# Sensor_Glove_Power-X02.net
KiCad netlist of a schematic drawn in Altium Designer
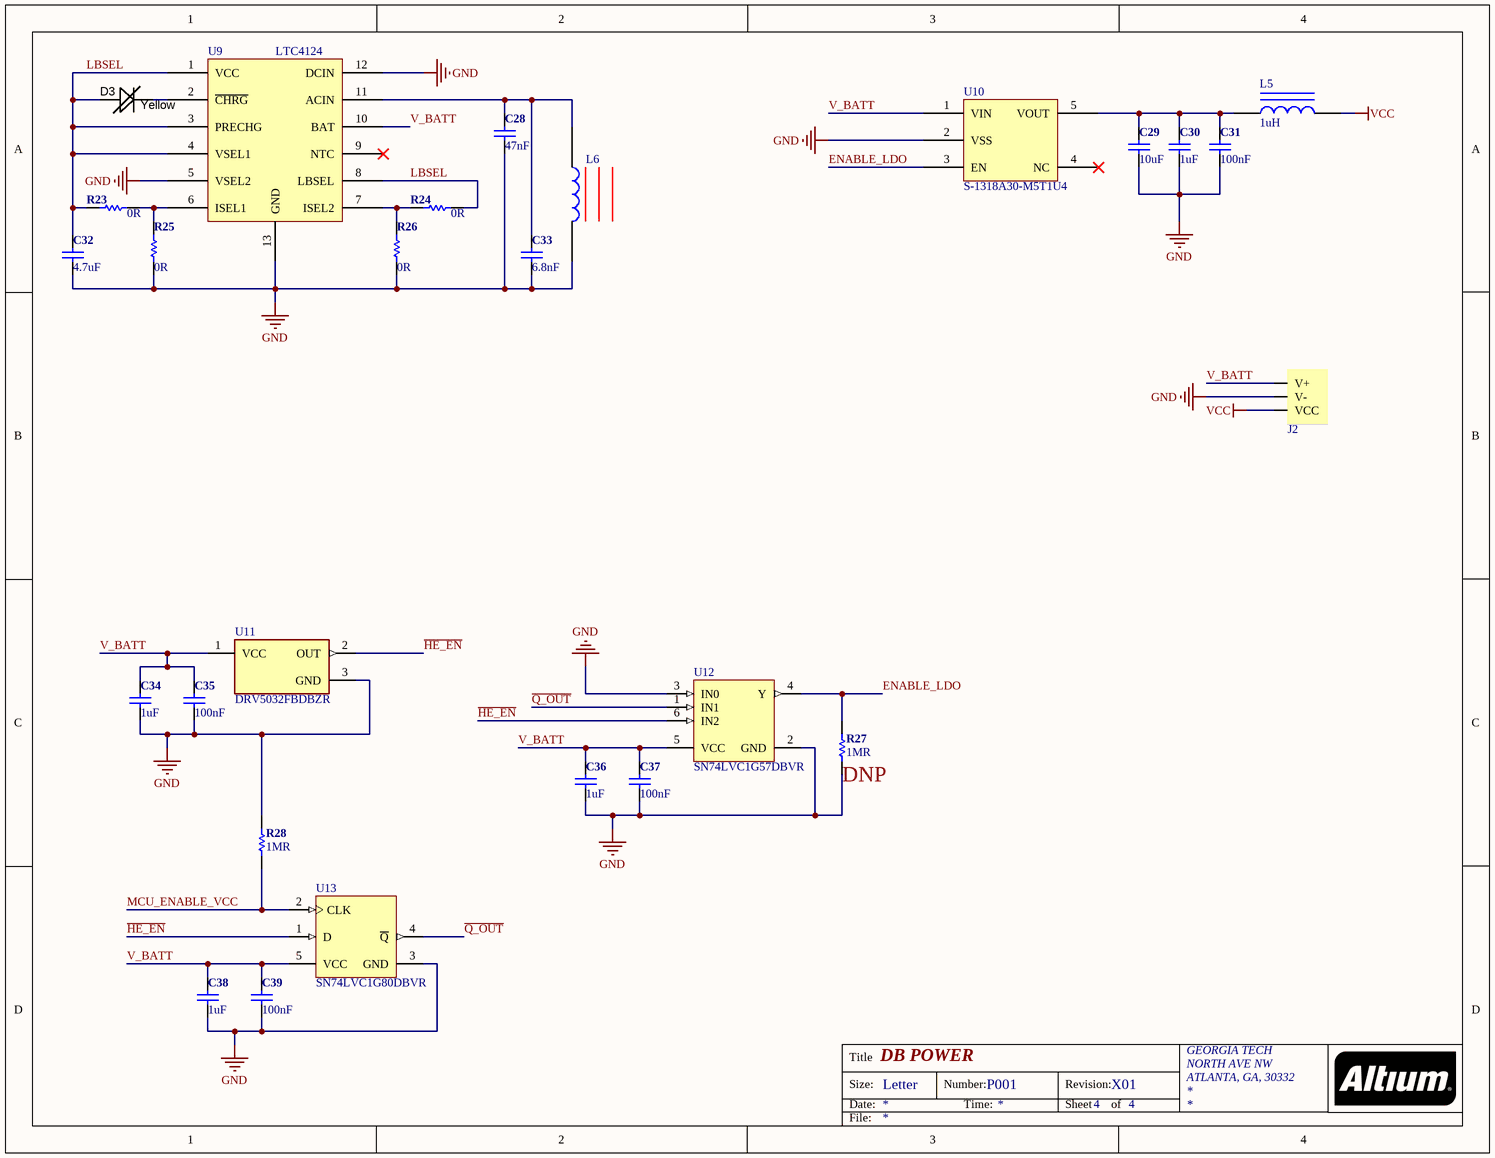
[diagram p0: Sensor_Glove_Power-X02.SchDoc]

(export (version "E")
  (design (tool "Eeschema 10.0.6"))
  (components
    (comp (ref "C28")
      (value "47nF")
      (footprint "C0402")
      (fields
        (field (name "MANUFACTURER") "Murata")
        (field (name "MANUFACTURER PART NUMBER") "GCM155R71H473KE02D")
      )
      (libsource (lib "LP_ECG-X02") (part "C-0402(1005)"))
    )
    (comp (ref "C29")
      (value "10uF")
      (footprint "C0402")
      (fields
        (field (name "MANUFACTURER") "Kyocera AVX")
        (field (name "MANUFACTURER PART NUMBER") "0402ZD106MAT2A")
      )
      (libsource (lib "LP_ECG-X01") (part "C-0402(1005)"))
    )
    (comp (ref "C30")
      (value "1uF")
      (footprint "C0402")
      (fields
        (field (name "MANUFACTURER") "Yageo")
        (field (name "MANUFACTURER PART NUMBER") "CC0402MRX5R5BB105")
        (field (name "TOLERANCE") "20%")
      )
      (libsource (lib "LP_ECG-X01") (part "C-0402(1005)"))
    )
    (comp (ref "C31")
      (value "100nF")
      (footprint "C0402")
      (fields
        (field (name "MANUFACTURER") "Taiyo Yuden")
        (field (name "MANUFACTURER PART NUMBER") "TMK105BJ104KV-F")
        (field (name "TOLERANCE") "10%")
      )
      (libsource (lib "LP_ECG-X01") (part "C-0402(1005)"))
    )
    (comp (ref "C32")
      (value "4.7uF")
      (footprint "C0402")
      (fields
        (field (name "MANUFACTURER") "Murata")
        (field (name "MANUFACTURER PART NUMBER") "GRM155R60J475ME87J")
      )
      (libsource (lib "LP_ECG-X02") (part "C-0402(1005)"))
    )
    (comp (ref "C33")
      (value "6.8nF")
      (footprint "C0402")
      (fields
        (field (name "MANUFACTURER") "Murata")
        (field (name "MANUFACTURER PART NUMBER") "GCM155R71H682KA55D")
      )
      (libsource (lib "LP_ECG-X02") (part "C-0402(1005)"))
    )
    (comp (ref "C34")
      (value "1uF")
      (footprint "C0402")
      (fields
        (field (name "MANUFACTURER") "Yageo")
        (field (name "MANUFACTURER PART NUMBER") "CC0402MRX5R5BB105")
        (field (name "TOLERANCE") "20%")
      )
      (libsource (lib "Sensor_Glove-X02") (part "C-0402(1005)"))
    )
    (comp (ref "C35")
      (value "100nF")
      (footprint "C0402")
      (fields
        (field (name "MANUFACTURER") "Taiyo Yuden")
        (field (name "MANUFACTURER PART NUMBER") "TMK105BJ104KV-F")
        (field (name "TOLERANCE") "10%")
      )
      (libsource (lib "LP_ECG-X01") (part "C-0402(1005)"))
    )
    (comp (ref "C36")
      (value "1uF")
      (footprint "C0402")
      (fields
        (field (name "MANUFACTURER") "Yageo")
        (field (name "MANUFACTURER PART NUMBER") "CC0402MRX5R5BB105")
        (field (name "TOLERANCE") "20%")
      )
      (libsource (lib "Sensor_Glove-X02") (part "C-0402(1005)"))
    )
    (comp (ref "C37")
      (value "100nF")
      (footprint "C0402")
      (fields
        (field (name "MANUFACTURER") "Taiyo Yuden")
        (field (name "MANUFACTURER PART NUMBER") "TMK105BJ104KV-F")
        (field (name "TOLERANCE") "10%")
      )
      (libsource (lib "LP_ECG-X01") (part "C-0402(1005)"))
    )
    (comp (ref "C38")
      (value "1uF")
      (footprint "C0402")
      (fields
        (field (name "MANUFACTURER") "Yageo")
        (field (name "MANUFACTURER PART NUMBER") "CC0402MRX5R5BB105")
        (field (name "TOLERANCE") "20%")
      )
      (libsource (lib "LP_ECG-X01") (part "C-0402(1005)"))
    )
    (comp (ref "C39")
      (value "100nF")
      (footprint "C0402")
      (fields
        (field (name "MANUFACTURER") "Taiyo Yuden")
        (field (name "MANUFACTURER PART NUMBER") "TMK105BJ104KV-F")
        (field (name "TOLERANCE") "10%")
      )
      (libsource (lib "LP_ECG-X01") (part "C-0402(1005)"))
    )
    (comp (ref "D3")
      (value "Yellow")
      (footprint "LED_0402")
      (description "Single Color LED, Super Bright Yellow, Water Clear, 0.8mm")
      (fields
        (field (name "MANUFACTURER") "Kingbright")
        (field (name "MANUFACTURER PART NUMBER") "APHHS1005SYCK")
      )
      (libsource (lib "Sensor_Glove-X02") (part "LED_0402(1005)"))
    )
    (comp (ref "J2")
      (value "SMD CONNECTOR FOR 40 mAh BATTERY")
      (footprint "battery_connector")
      (description "Lithium Battery 3.7V 40mAh Rechargeable")
      (libsource (lib "LP_ECG-X01") (part "SMD_BATTERY_CONNECTOR"))
    )
    (comp (ref "L5")
      (value "1uH")
      (footprint "L0402")
      (description "General Purpose Inductor, 1uH, 20%, 1 Element, Ferrite-Core, SMD, 0402")
      (fields
        (field (name "MANUFACTURER") "TDK")
        (field (name "MANUFACTURER PART NUMBER") "MLZ1005M1R0WT000")
      )
      (libsource (lib "LP_ECG-X01") (part "Inductor Iron"))
    )
    (comp (ref "L6")
      (value "WIRELESS CHARGING COIL, RECEIVER")
      (footprint "760308101219")
      (description "General Purpose Inductor, 11.8uH, 10%, 1 Element")
      (fields
        (field (name "MANUFACTURER") "Wurth Electronics")
        (field (name "MANUFACTURER PART NUMBER") "760308101219")
      )
      (libsource (lib "Sensor_Glove-X02") (part "WIRELESS_CHARGING_COIL"))
    )
    (comp (ref "R23")
      (value "0R")
      (footprint "R0402")
      (description "Fixed Resistor, Metal Glaze/thick Film, 0.0625W, 0ohm, Surface Mount, 0402")
      (fields
        (field (name "MANUFACTURER") "Yageo")
        (field (name "MANUFACTURER PART NUMBER") "AC0402JR-070RL")
      )
      (libsource (lib "LP_ECG-X02") (part "R-0402(1005)"))
    )
    (comp (ref "R24")
      (value "0R")
      (footprint "R0402")
      (description "Fixed Resistor, Metal Glaze/thick Film, 0.0625W, 0ohm, Surface Mount, 0402")
      (fields
        (field (name "MANUFACTURER") "Yageo")
        (field (name "MANUFACTURER PART NUMBER") "AC0402JR-070RL")
      )
      (libsource (lib "LP_ECG-X02") (part "R-0402(1005)"))
    )
    (comp (ref "R25")
      (value "0R")
      (footprint "R0402")
      (description "Fixed Resistor, Metal Glaze/thick Film, 0.0625W, 0ohm, Surface Mount, 0402")
      (fields
        (field (name "MANUFACTURER") "Yageo")
        (field (name "MANUFACTURER PART NUMBER") "AC0402JR-070RL")
      )
      (libsource (lib "LP_ECG-X02") (part "R-0402(1005)"))
    )
    (comp (ref "R26")
      (value "0R")
      (footprint "R0402")
      (description "Fixed Resistor, Metal Glaze/thick Film, 0.0625W, 0ohm, Surface Mount, 0402")
      (fields
        (field (name "MANUFACTURER") "Yageo")
        (field (name "MANUFACTURER PART NUMBER") "AC0402JR-070RL")
      )
      (libsource (lib "LP_ECG-X02") (part "R-0402(1005)"))
    )
    (comp (ref "R27")
      (value "1MR")
      (footprint "R0402")
      (fields
        (field (name "MANUFACTURER") "Yageo")
        (field (name "MANUFACTURER PART NUMBER") "AC0402FR-071ML")
        (field (name "TOLERANCE") "1%")
      )
      (libsource (lib "LP_ECG-X01") (part "R-0402(1005)"))
    )
    (comp (ref "R28")
      (value "1MR")
      (footprint "R0402")
      (fields
        (field (name "MANUFACTURER") "Yageo")
        (field (name "MANUFACTURER PART NUMBER") "AC0402FR-071ML")
        (field (name "TOLERANCE") "1%")
      )
      (libsource (lib "LP_ECG-X01") (part "R-0402(1005)"))
    )
    (comp (ref "U9")
      (value "LTC4124")
      (footprint "12-LQFN")
      (description "Power Supply Support Circuit, Adjustable, 1 Channel, CMOS")
      (fields
        (field (name "MANUFACTURER") "Analog Devices")
        (field (name "MANUFACTURER PART NUMBER") "LTC4124EV#TRMPBF")
      )
      (libsource (lib "LP_ECG-X02") (part "LTC4124"))
    )
    (comp (ref "U10")
      (value "S-1318A30-M5T1U4")
      (footprint "SOT-23-5")
      (description "Fixed Positive LDO Regulator")
      (fields (field (name "MANUFACTURER") "ABLIC"))
      (libsource (lib "LP_ECG-X02") (part "S-1318A30-M5T1U4"))
    )
    (comp (ref "U11")
      (value "DRV5032FBDBZR")
      (footprint "FP-DBZ0003A-MFG")
      (description "LP HALL 32FBDBZR")
      (fields (field (name "MANUFACTURER") "Texas Instruments"))
      (libsource (lib "Altium Content Vault") (part "2ac151be60cf6bda0d169f73a696793"))
    )
    (comp (ref "U12")
      (value "SN74LVC1G57DBVR")
      (footprint "DBV0006A_M")
      (description "CONFIGURABLE MULTIPLE-FUNCTION GATE, DBV0006A, LARGE T&R")
      (fields (field (name "MANUFACTURER") "Texas Instruments"))
      (libsource (lib "Altium Content Vault") (part "TI-SN74XXX1GXX-6"))
    )
    (comp (ref "U13")
      (value "SN74LVC1G80DBVR")
      (footprint "DBV0005A_N")
      (description "Single Positive-Edge-Triggered D-Type Flip-Flop, DBV0005A, LARGE T&R")
      (fields (field (name "MANUFACTURER") "Texas Instruments"))
      (libsource (lib "Altium Content Vault") (part "TI-SN74XXX1G80-5"))
    )
  )
  (nets
    (net (code "1") (name "/ENABLE_LDO") (class "Default")
      (node (ref "R27") (pin "1") (pinfunction "1_1") (pintype "passive"))
      (node (ref "U10") (pin "3") (pinfunction "EN_3") (pintype "passive"))
      (node (ref "U12") (pin "4") (pinfunction "Y_4") (pintype "output"))
    )
    (net (code "2") (name "/LBSEL") (class "Default")
      (node (ref "C32") (pin "1") (pinfunction "1_1") (pintype "passive"))
      (node (ref "D3") (pin "A") (pinfunction "A_A") (pintype "passive"))
      (node (ref "R23") (pin "1") (pinfunction "1_1") (pintype "passive"))
      (node (ref "R24") (pin "2") (pinfunction "2_2") (pintype "passive"))
      (node (ref "U9") (pin "1") (pinfunction "VCC_1") (pintype "passive"))
      (node (ref "U9") (pin "3") (pinfunction "PRECHG_3") (pintype "passive"))
      (node (ref "U9") (pin "4") (pinfunction "VSEL1_4") (pintype "passive"))
      (node (ref "U9") (pin "8") (pinfunction "LBSEL_8") (pintype "passive"))
    )
    (net (code "3") (name "/MCU_ENABLE_VCC") (class "Default")
      (node (ref "R28") (pin "2") (pinfunction "2_2") (pintype "passive"))
      (node (ref "U13") (pin "2") (pinfunction "CLK_2") (pintype "input"))
    )
    (net (code "4") (name "/V_BATT") (class "Default")
      (node (ref "C34") (pin "1") (pinfunction "1_1") (pintype "passive"))
      (node (ref "C35") (pin "2") (pinfunction "2_2") (pintype "passive"))
      (node (ref "C36") (pin "1") (pinfunction "1_1") (pintype "passive"))
      (node (ref "C37") (pin "2") (pinfunction "2_2") (pintype "passive"))
      (node (ref "C38") (pin "1") (pinfunction "1_1") (pintype "passive"))
      (node (ref "C39") (pin "2") (pinfunction "2_2") (pintype "passive"))
      (node (ref "J2") (pin "1") (pinfunction "V+_1") (pintype "power_in"))
      (node (ref "U10") (pin "1") (pinfunction "VIN_1") (pintype "passive"))
      (node (ref "U11") (pin "1") (pinfunction "VCC_1") (pintype "power_in"))
      (node (ref "U12") (pin "5") (pinfunction "VCC_5") (pintype "power_in"))
      (node (ref "U13") (pin "5") (pinfunction "VCC_5") (pintype "power_in"))
      (node (ref "U9") (pin "10") (pinfunction "BAT_10") (pintype "passive"))
    )
    (net (code "5") (name "/~{HE_EN}") (class "Default")
      (node (ref "U11") (pin "2") (pinfunction "OUT_2") (pintype "output"))
      (node (ref "U12") (pin "6") (pinfunction "IN2_6") (pintype "input"))
      (node (ref "U13") (pin "1") (pinfunction "D_1") (pintype "input"))
    )
    (net (code "6") (name "/~{Q_OUT}") (class "Default")
      (node (ref "U12") (pin "1") (pinfunction "IN1_1") (pintype "input"))
      (node (ref "U13") (pin "4") (pinfunction "~{Q}_4") (pintype "output"))
    )
    (net (code "7") (name "GND") (class "Default")
      (node (ref "C28") (pin "2") (pinfunction "2_2") (pintype "passive"))
      (node (ref "C29") (pin "2") (pinfunction "2_2") (pintype "passive"))
      (node (ref "C30") (pin "2") (pinfunction "2_2") (pintype "passive"))
      (node (ref "C31") (pin "1") (pinfunction "1_1") (pintype "passive"))
      (node (ref "C32") (pin "2") (pinfunction "2_2") (pintype "passive"))
      (node (ref "C33") (pin "2") (pinfunction "2_2") (pintype "passive"))
      (node (ref "C34") (pin "2") (pinfunction "2_2") (pintype "passive"))
      (node (ref "C35") (pin "1") (pinfunction "1_1") (pintype "passive"))
      (node (ref "C36") (pin "2") (pinfunction "2_2") (pintype "passive"))
      (node (ref "C37") (pin "1") (pinfunction "1_1") (pintype "passive"))
      (node (ref "C38") (pin "2") (pinfunction "2_2") (pintype "passive"))
      (node (ref "C39") (pin "1") (pinfunction "1_1") (pintype "passive"))
      (node (ref "J2") (pin "2") (pinfunction "V-_2") (pintype "power_in"))
      (node (ref "L6") (pin "2") (pinfunction "2_2") (pintype "passive"))
      (node (ref "R25") (pin "2") (pinfunction "2_2") (pintype "passive"))
      (node (ref "R26") (pin "2") (pinfunction "2_2") (pintype "passive"))
      (node (ref "R27") (pin "2") (pinfunction "2_2") (pintype "passive"))
      (node (ref "R28") (pin "1") (pinfunction "1_1") (pintype "passive"))
      (node (ref "U10") (pin "2") (pinfunction "VSS_2") (pintype "passive"))
      (node (ref "U11") (pin "3") (pinfunction "GND_3") (pintype "power_in"))
      (node (ref "U12") (pin "2") (pinfunction "GND_2") (pintype "power_in"))
      (node (ref "U12") (pin "3") (pinfunction "IN0_3") (pintype "input"))
      (node (ref "U13") (pin "3") (pinfunction "GND_3") (pintype "power_in"))
      (node (ref "U9") (pin "12") (pinfunction "DCIN_12") (pintype "passive"))
      (node (ref "U9") (pin "13") (pinfunction "GND_13") (pintype "passive"))
      (node (ref "U9") (pin "5") (pinfunction "VSEL2_5") (pintype "passive"))
    )
    (net (code "8") (name "Net-(U9-ACIN)") (class "Default")
      (node (ref "C28") (pin "1") (pinfunction "1_1") (pintype "passive"))
      (node (ref "C33") (pin "1") (pinfunction "1_1") (pintype "passive"))
      (node (ref "L6") (pin "1") (pinfunction "1_1") (pintype "passive"))
      (node (ref "U9") (pin "11") (pinfunction "ACIN_11") (pintype "passive"))
    )
    (net (code "9") (name "Net-(U9-ISEL1)") (class "Default")
      (node (ref "R23") (pin "2") (pinfunction "2_2") (pintype "passive"))
      (node (ref "R25") (pin "1") (pinfunction "1_1") (pintype "passive"))
      (node (ref "U9") (pin "6") (pinfunction "ISEL1_6") (pintype "passive"))
    )
    (net (code "10") (name "Net-(U9-ISEL2)") (class "Default")
      (node (ref "R24") (pin "1") (pinfunction "1_1") (pintype "passive"))
      (node (ref "R26") (pin "1") (pinfunction "1_1") (pintype "passive"))
      (node (ref "U9") (pin "7") (pinfunction "ISEL2_7") (pintype "passive"))
    )
    (net (code "11") (name "Net-(U9-~{CHRG})") (class "Default")
      (node (ref "D3") (pin "K") (pinfunction "K_K") (pintype "passive"))
      (node (ref "U9") (pin "2") (pinfunction "~{CHRG}_2") (pintype "passive"))
    )
    (net (code "12") (name "Net-(U10-VOUT)") (class "Default")
      (node (ref "C29") (pin "1") (pinfunction "1_1") (pintype "passive"))
      (node (ref "C30") (pin "1") (pinfunction "1_1") (pintype "passive"))
      (node (ref "C31") (pin "2") (pinfunction "2_2") (pintype "passive"))
      (node (ref "L5") (pin "1") (pinfunction "1_1") (pintype "passive"))
      (node (ref "U10") (pin "5") (pinfunction "VOUT_5") (pintype "passive"))
    )
    (net (code "13") (name "VCC") (class "Default")
      (node (ref "J2") (pin "3") (pinfunction "VCC_3") (pintype "power_in"))
      (node (ref "L5") (pin "2") (pinfunction "2_2") (pintype "passive"))
    )
    (net (code "14") (name "unconnected-(U9-NTC-Pad9)") (class "Default")
      (node (ref "U9") (pin "9") (pinfunction "NTC_9") (pintype "passive+no_connect"))
    )
    (net (code "15") (name "unconnected-(U10-NC-Pad4)") (class "Default")
      (node (ref "U10") (pin "4") (pinfunction "NC_4") (pintype "passive+no_connect"))
    )
  )
)
